# VGA_Buddy_PCB.net
KiCad netlist of a schematic drawn in Altium Designer
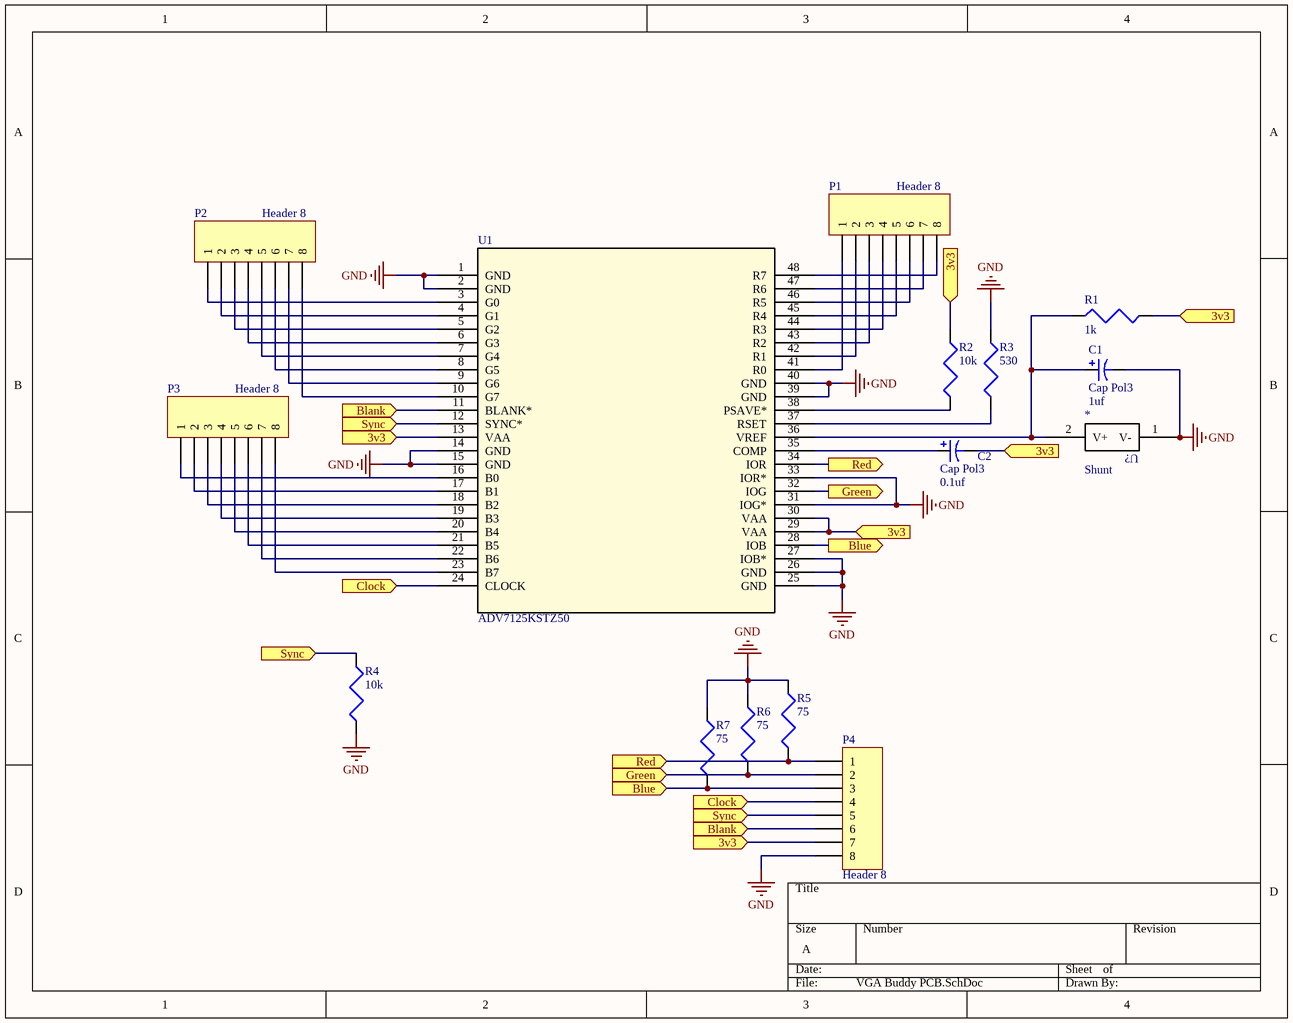
[diagram p0: VGA Buddy PCB.SchDoc]

(export (version "E")
  (design (tool "Eeschema 10.0.6"))
  (components
    (comp (ref "*") (value "Shunt") (footprint "SOT95P245X110-3N") (libsource (lib "Schlib1") (part "Shunt")))
    (comp (ref "C1")
      (value "Cap Pol3")
      (footprint "C0805")
      (description "Polarized Capacitor (Surface Mount)")
      (fields (field (name "ALTIUM_VALUE") "1uf") (field (name "PUBLISHER") "Altium Limited"))
      (libsource (lib "Miscellaneous Devices") (part "Cap Pol3"))
    )
    (comp (ref "C2")
      (value "Cap Pol3")
      (footprint "C0805")
      (description "Polarized Capacitor (Surface Mount)")
      (fields (field (name "ALTIUM_VALUE") "0.1uf") (field (name "PUBLISHER") "Altium Limited"))
      (libsource (lib "Miscellaneous Devices") (part "Cap Pol3"))
    )
    (comp (ref "P1")
      (value "Header 8")
      (footprint "HDR1X8")
      (description "Header, 8-Pin")
      (fields (field (name "PUBLISHER") "Altium Limited"))
      (libsource (lib "Miscellaneous Connectors") (part "Header 8"))
    )
    (comp (ref "P2")
      (value "Header 8")
      (footprint "HDR1X8")
      (description "Header, 8-Pin")
      (fields (field (name "PUBLISHER") "Altium Limited"))
      (libsource (lib "Miscellaneous Connectors") (part "Header 8"))
    )
    (comp (ref "P3")
      (value "Header 8")
      (footprint "HDR1X8")
      (description "Header, 8-Pin")
      (fields (field (name "PUBLISHER") "Altium Limited"))
      (libsource (lib "Miscellaneous Connectors") (part "Header 8"))
    )
    (comp (ref "P4")
      (value "Header 8")
      (footprint "HDR1X8")
      (description "Header, 8-Pin")
      (fields (field (name "PUBLISHER") "Altium Limited"))
      (libsource (lib "") (part "Header 8_1"))
    )
    (comp (ref "R1") (value "1k") (footprint "805") (libsource (lib "Schlib1") (part "1k")))
    (comp (ref "R2") (value "10k") (footprint "805") (libsource (lib "Schlib1") (part "1k")))
    (comp (ref "R3") (value "530") (footprint "805") (libsource (lib "Schlib1") (part "1k")))
    (comp (ref "R4") (value "10k") (footprint "805") (libsource (lib "Schlib1") (part "1k")))
    (comp (ref "R5") (value "75") (footprint "805") (libsource (lib "Schlib1") (part "1k")))
    (comp (ref "R6") (value "75") (footprint "805") (libsource (lib "Schlib1") (part "1k")))
    (comp (ref "R7") (value "75") (footprint "805") (libsource (lib "Schlib1") (part "1k")))
    (comp (ref "U1")
      (value "ADV7125KSTZ50")
      (footprint "ST_48_ADI")
      (description "No Description Available")
      (fields (field (name "COPYRIGHT") "Copyright (C) 2018 Accelerated Designs. All rights reserved"))
      (libsource (lib "2020-09-26_17-27-19") (part "ADV7125KSTZ50"))
    )
  )
  (nets
    (net (code "1") (name "/3v3") (class "Default")
      (node (ref "C2") (pin "2") (pinfunction "2_2") (pintype "passive"))
      (node (ref "P4") (pin "7") (pinfunction "7_7") (pintype "passive"))
      (node (ref "R1") (pin "2") (pinfunction "53_2") (pintype "passive"))
      (node (ref "R2") (pin "2") (pinfunction "53_2") (pintype "passive"))
      (node (ref "U1") (pin "13") (pinfunction "VAA_13") (pintype "power_in"))
      (node (ref "U1") (pin "29") (pinfunction "VAA_29") (pintype "power_in"))
      (node (ref "U1") (pin "30") (pinfunction "VAA_30") (pintype "power_in"))
    )
    (net (code "2") (name "/Blank") (class "Default")
      (node (ref "P4") (pin "6") (pinfunction "6_6") (pintype "passive"))
      (node (ref "U1") (pin "11") (pinfunction "BLANK*_11") (pintype "passive"))
    )
    (net (code "3") (name "/Blue") (class "Default")
      (node (ref "P4") (pin "3") (pinfunction "3_3") (pintype "passive"))
      (node (ref "R7") (pin "1") (pinfunction "52_1") (pintype "passive"))
      (node (ref "U1") (pin "28") (pinfunction "IOB_28") (pintype "passive"))
    )
    (net (code "4") (name "/Clock") (class "Default")
      (node (ref "P4") (pin "4") (pinfunction "4_4") (pintype "passive"))
      (node (ref "U1") (pin "24") (pinfunction "CLOCK_24") (pintype "passive"))
    )
    (net (code "5") (name "/Green") (class "Default")
      (node (ref "P4") (pin "2") (pinfunction "2_2") (pintype "passive"))
      (node (ref "R6") (pin "1") (pinfunction "52_1") (pintype "passive"))
      (node (ref "U1") (pin "32") (pinfunction "IOG_32") (pintype "passive"))
    )
    (net (code "6") (name "/Red") (class "Default")
      (node (ref "P4") (pin "1") (pinfunction "1_1") (pintype "passive"))
      (node (ref "R5") (pin "1") (pinfunction "52_1") (pintype "passive"))
      (node (ref "U1") (pin "34") (pinfunction "IOR_34") (pintype "passive"))
    )
    (net (code "7") (name "/Sync") (class "Default")
      (node (ref "P4") (pin "5") (pinfunction "5_5") (pintype "passive"))
      (node (ref "R4") (pin "2") (pinfunction "53_2") (pintype "passive"))
      (node (ref "U1") (pin "12") (pinfunction "SYNC*_12") (pintype "passive"))
    )
    (net (code "8") (name "GND") (class "Default")
      (node (ref "*") (pin "1") (pinfunction "V-_1") (pintype "passive"))
      (node (ref "C1") (pin "2") (pinfunction "2_2") (pintype "passive"))
      (node (ref "P4") (pin "8") (pinfunction "8_8") (pintype "passive"))
      (node (ref "R3") (pin "2") (pinfunction "53_2") (pintype "passive"))
      (node (ref "R4") (pin "1") (pinfunction "52_1") (pintype "passive"))
      (node (ref "R5") (pin "2") (pinfunction "53_2") (pintype "passive"))
      (node (ref "R6") (pin "2") (pinfunction "53_2") (pintype "passive"))
      (node (ref "R7") (pin "2") (pinfunction "53_2") (pintype "passive"))
      (node (ref "U1") (pin "1") (pinfunction "GND_1") (pintype "passive"))
      (node (ref "U1") (pin "14") (pinfunction "GND_14") (pintype "passive"))
      (node (ref "U1") (pin "15") (pinfunction "GND_15") (pintype "passive"))
      (node (ref "U1") (pin "2") (pinfunction "GND_2") (pintype "passive"))
      (node (ref "U1") (pin "25") (pinfunction "GND_25") (pintype "passive"))
      (node (ref "U1") (pin "26") (pinfunction "GND_26") (pintype "passive"))
      (node (ref "U1") (pin "27") (pinfunction "IOB*_27") (pintype "passive"))
      (node (ref "U1") (pin "31") (pinfunction "IOG*_31") (pintype "passive"))
      (node (ref "U1") (pin "33") (pinfunction "IOR*_33") (pintype "passive"))
      (node (ref "U1") (pin "39") (pinfunction "GND_39") (pintype "passive"))
      (node (ref "U1") (pin "40") (pinfunction "GND_40") (pintype "passive"))
    )
    (net (code "9") (name "Net-(*-V+)") (class "Default")
      (node (ref "*") (pin "2") (pinfunction "V+_2") (pintype "passive"))
      (node (ref "C1") (pin "1") (pinfunction "1_1") (pintype "passive"))
      (node (ref "R1") (pin "1") (pinfunction "52_1") (pintype "passive"))
      (node (ref "U1") (pin "36") (pinfunction "VREF_36") (pintype "passive"))
    )
    (net (code "10") (name "Net-(R2-52)") (class "Default")
      (node (ref "R2") (pin "1") (pinfunction "52_1") (pintype "passive"))
      (node (ref "U1") (pin "38") (pinfunction "PSAVE*_38") (pintype "passive"))
    )
    (net (code "11") (name "Net-(R3-52)") (class "Default")
      (node (ref "R3") (pin "1") (pinfunction "52_1") (pintype "passive"))
      (node (ref "U1") (pin "37") (pinfunction "RSET_37") (pintype "passive"))
    )
    (net (code "12") (name "Net-(U1-B0)") (class "Default")
      (node (ref "P3") (pin "1") (pinfunction "1_1") (pintype "passive"))
      (node (ref "U1") (pin "16") (pinfunction "B0_16") (pintype "passive"))
    )
    (net (code "13") (name "Net-(U1-B1)") (class "Default")
      (node (ref "P3") (pin "2") (pinfunction "2_2") (pintype "passive"))
      (node (ref "U1") (pin "17") (pinfunction "B1_17") (pintype "passive"))
    )
    (net (code "14") (name "Net-(U1-B2)") (class "Default")
      (node (ref "P3") (pin "3") (pinfunction "3_3") (pintype "passive"))
      (node (ref "U1") (pin "18") (pinfunction "B2_18") (pintype "passive"))
    )
    (net (code "15") (name "Net-(U1-B3)") (class "Default")
      (node (ref "P3") (pin "4") (pinfunction "4_4") (pintype "passive"))
      (node (ref "U1") (pin "19") (pinfunction "B3_19") (pintype "passive"))
    )
    (net (code "16") (name "Net-(U1-B4)") (class "Default")
      (node (ref "P3") (pin "5") (pinfunction "5_5") (pintype "passive"))
      (node (ref "U1") (pin "20") (pinfunction "B4_20") (pintype "passive"))
    )
    (net (code "17") (name "Net-(U1-B5)") (class "Default")
      (node (ref "P3") (pin "6") (pinfunction "6_6") (pintype "passive"))
      (node (ref "U1") (pin "21") (pinfunction "B5_21") (pintype "passive"))
    )
    (net (code "18") (name "Net-(U1-B6)") (class "Default")
      (node (ref "P3") (pin "7") (pinfunction "7_7") (pintype "passive"))
      (node (ref "U1") (pin "22") (pinfunction "B6_22") (pintype "passive"))
    )
    (net (code "19") (name "Net-(U1-B7)") (class "Default")
      (node (ref "P3") (pin "8") (pinfunction "8_8") (pintype "passive"))
      (node (ref "U1") (pin "23") (pinfunction "B7_23") (pintype "passive"))
    )
    (net (code "20") (name "Net-(U1-COMP)") (class "Default")
      (node (ref "C2") (pin "1") (pinfunction "1_1") (pintype "passive"))
      (node (ref "U1") (pin "35") (pinfunction "COMP_35") (pintype "passive"))
    )
    (net (code "21") (name "Net-(U1-G0)") (class "Default")
      (node (ref "P2") (pin "1") (pinfunction "1_1") (pintype "passive"))
      (node (ref "U1") (pin "3") (pinfunction "G0_3") (pintype "passive"))
    )
    (net (code "22") (name "Net-(U1-G1)") (class "Default")
      (node (ref "P2") (pin "2") (pinfunction "2_2") (pintype "passive"))
      (node (ref "U1") (pin "4") (pinfunction "G1_4") (pintype "passive"))
    )
    (net (code "23") (name "Net-(U1-G2)") (class "Default")
      (node (ref "P2") (pin "3") (pinfunction "3_3") (pintype "passive"))
      (node (ref "U1") (pin "5") (pinfunction "G2_5") (pintype "passive"))
    )
    (net (code "24") (name "Net-(U1-G3)") (class "Default")
      (node (ref "P2") (pin "4") (pinfunction "4_4") (pintype "passive"))
      (node (ref "U1") (pin "6") (pinfunction "G3_6") (pintype "passive"))
    )
    (net (code "25") (name "Net-(U1-G4)") (class "Default")
      (node (ref "P2") (pin "5") (pinfunction "5_5") (pintype "passive"))
      (node (ref "U1") (pin "7") (pinfunction "G4_7") (pintype "passive"))
    )
    (net (code "26") (name "Net-(U1-G5)") (class "Default")
      (node (ref "P2") (pin "6") (pinfunction "6_6") (pintype "passive"))
      (node (ref "U1") (pin "8") (pinfunction "G5_8") (pintype "passive"))
    )
    (net (code "27") (name "Net-(U1-G6)") (class "Default")
      (node (ref "P2") (pin "7") (pinfunction "7_7") (pintype "passive"))
      (node (ref "U1") (pin "9") (pinfunction "G6_9") (pintype "passive"))
    )
    (net (code "28") (name "Net-(U1-G7)") (class "Default")
      (node (ref "P2") (pin "8") (pinfunction "8_8") (pintype "passive"))
      (node (ref "U1") (pin "10") (pinfunction "G7_10") (pintype "passive"))
    )
    (net (code "29") (name "Net-(U1-R0)") (class "Default")
      (node (ref "P1") (pin "1") (pinfunction "1_1") (pintype "passive"))
      (node (ref "U1") (pin "41") (pinfunction "R0_41") (pintype "passive"))
    )
    (net (code "30") (name "Net-(U1-R1)") (class "Default")
      (node (ref "P1") (pin "2") (pinfunction "2_2") (pintype "passive"))
      (node (ref "U1") (pin "42") (pinfunction "R1_42") (pintype "passive"))
    )
    (net (code "31") (name "Net-(U1-R2)") (class "Default")
      (node (ref "P1") (pin "3") (pinfunction "3_3") (pintype "passive"))
      (node (ref "U1") (pin "43") (pinfunction "R2_43") (pintype "passive"))
    )
    (net (code "32") (name "Net-(U1-R3)") (class "Default")
      (node (ref "P1") (pin "4") (pinfunction "4_4") (pintype "passive"))
      (node (ref "U1") (pin "44") (pinfunction "R3_44") (pintype "passive"))
    )
    (net (code "33") (name "Net-(U1-R4)") (class "Default")
      (node (ref "P1") (pin "5") (pinfunction "5_5") (pintype "passive"))
      (node (ref "U1") (pin "45") (pinfunction "R4_45") (pintype "passive"))
    )
    (net (code "34") (name "Net-(U1-R5)") (class "Default")
      (node (ref "P1") (pin "6") (pinfunction "6_6") (pintype "passive"))
      (node (ref "U1") (pin "46") (pinfunction "R5_46") (pintype "passive"))
    )
    (net (code "35") (name "Net-(U1-R6)") (class "Default")
      (node (ref "P1") (pin "7") (pinfunction "7_7") (pintype "passive"))
      (node (ref "U1") (pin "47") (pinfunction "R6_47") (pintype "passive"))
    )
    (net (code "36") (name "Net-(U1-R7)") (class "Default")
      (node (ref "P1") (pin "8") (pinfunction "8_8") (pintype "passive"))
      (node (ref "U1") (pin "48") (pinfunction "R7_48") (pintype "passive"))
    )
  )
)
